# Sheet1.net
KiCad netlist of a schematic drawn in Altium Designer
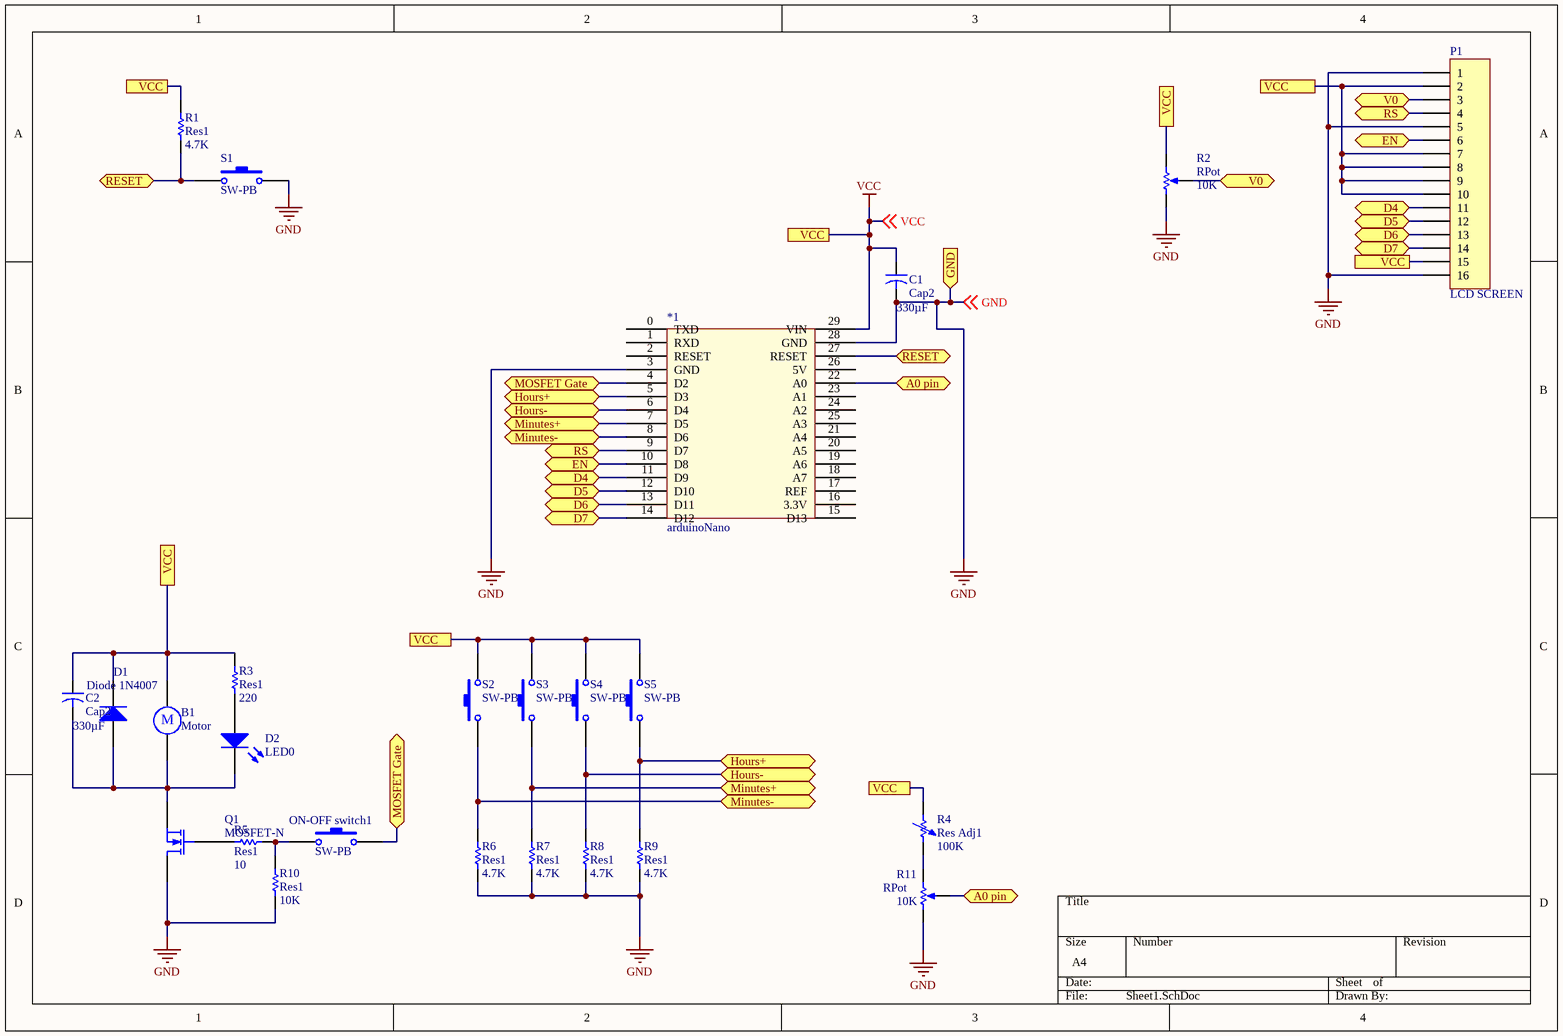
[diagram p0: Sheet1.SchDoc]

(export (version "E")
  (design (tool "Eeschema 10.0.6"))
  (components
    (comp (ref "*1")
      (value "arduinoNano")
      (footprint "Arduino nano")
      (libsource (lib "nanoArduino") (part "arduinoNano"))
    )
    (comp (ref "B1")
      (value "Motor")
      (footprint "RB5-10.5")
      (description "Motor, General Kind")
      (fields (field (name "PUBLISHER") "Altium Limited"))
      (libsource (lib "Miscellaneous Devices") (part "Motor"))
    )
    (comp (ref "C1")
      (value "Cap2")
      (footprint "CAPR5-4X5")
      (description "Capacitor")
      (fields (field (name "ALTIUM_VALUE") "330µF") (field (name "PUBLISHER") "Altium Limited"))
      (libsource (lib "Miscellaneous Devices") (part "Cap2"))
    )
    (comp (ref "C2")
      (value "Cap2")
      (footprint "CAPR5-4X5")
      (description "Capacitor")
      (fields (field (name "ALTIUM_VALUE") "330µF") (field (name "PUBLISHER") "Altium Limited"))
      (libsource (lib "Miscellaneous Devices") (part "Cap2"))
    )
    (comp (ref "D1")
      (value "Diode 1N4007")
      (footprint "DO-41")
      (description "1 Amp General Purpose Rectifier")
      (fields (field (name "PUBLISHER") "Altium Limited"))
      (libsource (lib "Miscellaneous Devices") (part "Diode 1N4007"))
    )
    (comp (ref "D2")
      (value "LED0")
      (footprint "LED-0")
      (description "Typical INFRARED GaAs LED")
      (fields (field (name "PUBLISHER") "Altium Limited"))
      (libsource (lib "Miscellaneous Devices") (part "LED0"))
    )
    (comp (ref "ON-OFF switch1")
      (value "SW-PB")
      (footprint "SPST-2")
      (description "Switch")
      (fields (field (name "PUBLISHER") "Altium Limited"))
      (libsource (lib "Miscellaneous Devices") (part "SW-PB"))
    )
    (comp (ref "P1")
      (value "LCD SCREEN")
      (footprint "HDR1X16")
      (description "Header, 16-Pin")
      (fields (field (name "PUBLISHER") "Altium Limited"))
      (libsource (lib "Miscellaneous Connectors") (part "Header 16"))
    )
    (comp (ref "Q1")
      (value "MOSFET-N")
      (footprint "E3")
      (description "N-Channel MOSFET")
      (fields (field (name "PUBLISHER") "Altium Limited"))
      (libsource (lib "Miscellaneous Devices") (part "MOSFET-N"))
    )
    (comp (ref "R1")
      (value "Res1")
      (footprint "AXIAL-0.3")
      (description "Resistor")
      (fields (field (name "ALTIUM_VALUE") "4.7K") (field (name "PUBLISHER") "Altium Limited"))
      (libsource (lib "Miscellaneous Devices") (part "Res1"))
    )
    (comp (ref "R2")
      (value "RPot")
      (footprint "VR5")
      (description "Potentiometer")
      (fields (field (name "ALTIUM_VALUE") "10K") (field (name "PUBLISHER") "Altium Limited"))
      (libsource (lib "Miscellaneous Devices") (part "RPot"))
    )
    (comp (ref "R3")
      (value "Res1")
      (footprint "AXIAL-0.3")
      (description "Resistor")
      (fields (field (name "ALTIUM_VALUE") "220") (field (name "PUBLISHER") "Altium Limited"))
      (libsource (lib "Miscellaneous Devices") (part "Res1"))
    )
    (comp (ref "R4")
      (value "Res Adj1")
      (footprint "AXIAL-0.7")
      (description "Variable Resistor")
      (fields (field (name "ALTIUM_VALUE") "100K") (field (name "PUBLISHER") "Altium Limited"))
      (libsource (lib "Miscellaneous Devices") (part "Res Adj1"))
    )
    (comp (ref "R5")
      (value "Res1")
      (footprint "AXIAL-0.3")
      (description "Resistor")
      (fields (field (name "ALTIUM_VALUE") "10") (field (name "PUBLISHER") "Altium Limited"))
      (libsource (lib "Miscellaneous Devices") (part "Res1"))
    )
    (comp (ref "R6")
      (value "Res1")
      (footprint "AXIAL-0.3")
      (description "Resistor")
      (fields (field (name "ALTIUM_VALUE") "4.7K") (field (name "PUBLISHER") "Altium Limited"))
      (libsource (lib "Miscellaneous Devices") (part "Res1"))
    )
    (comp (ref "R7")
      (value "Res1")
      (footprint "AXIAL-0.3")
      (description "Resistor")
      (fields (field (name "ALTIUM_VALUE") "4.7K") (field (name "PUBLISHER") "Altium Limited"))
      (libsource (lib "Miscellaneous Devices") (part "Res1"))
    )
    (comp (ref "R8")
      (value "Res1")
      (footprint "AXIAL-0.3")
      (description "Resistor")
      (fields (field (name "ALTIUM_VALUE") "4.7K") (field (name "PUBLISHER") "Altium Limited"))
      (libsource (lib "Miscellaneous Devices") (part "Res1"))
    )
    (comp (ref "R9")
      (value "Res1")
      (footprint "AXIAL-0.3")
      (description "Resistor")
      (fields (field (name "ALTIUM_VALUE") "4.7K") (field (name "PUBLISHER") "Altium Limited"))
      (libsource (lib "Miscellaneous Devices") (part "Res1"))
    )
    (comp (ref "R10")
      (value "Res1")
      (footprint "AXIAL-0.3")
      (description "Resistor")
      (fields (field (name "ALTIUM_VALUE") "10K") (field (name "PUBLISHER") "Altium Limited"))
      (libsource (lib "Miscellaneous Devices") (part "Res1"))
    )
    (comp (ref "R11")
      (value "RPot")
      (footprint "VR5")
      (description "Potentiometer")
      (fields (field (name "ALTIUM_VALUE") "10K") (field (name "PUBLISHER") "Altium Limited"))
      (libsource (lib "Miscellaneous Devices") (part "RPot"))
    )
    (comp (ref "S1")
      (value "SW-PB")
      (footprint "SPST-2")
      (description "Switch")
      (fields (field (name "PUBLISHER") "Altium Limited"))
      (libsource (lib "Miscellaneous Devices") (part "SW-PB"))
    )
    (comp (ref "S2")
      (value "SW-PB")
      (footprint "SPST-2")
      (description "Switch")
      (fields (field (name "PUBLISHER") "Altium Limited"))
      (libsource (lib "Miscellaneous Devices") (part "SW-PB"))
    )
    (comp (ref "S3")
      (value "SW-PB")
      (footprint "SPST-2")
      (description "Switch")
      (fields (field (name "PUBLISHER") "Altium Limited"))
      (libsource (lib "Miscellaneous Devices") (part "SW-PB"))
    )
    (comp (ref "S4")
      (value "SW-PB")
      (footprint "SPST-2")
      (description "Switch")
      (fields (field (name "PUBLISHER") "Altium Limited"))
      (libsource (lib "Miscellaneous Devices") (part "SW-PB"))
    )
    (comp (ref "S5")
      (value "SW-PB")
      (footprint "SPST-2")
      (description "Switch")
      (fields (field (name "PUBLISHER") "Altium Limited"))
      (libsource (lib "Miscellaneous Devices") (part "SW-PB"))
    )
  )
  (nets
    (net (code "1") (name "/A0 pin") (class "Default")
      (node (ref "*1") (pin "22") (pinfunction "A0_22") (pintype "passive"))
      (node (ref "R11") (pin "3") (pinfunction "TAP_3") (pintype "passive"))
    )
    (net (code "2") (name "/D4") (class "Default")
      (node (ref "*1") (pin "11") (pinfunction "D9_11") (pintype "passive"))
      (node (ref "P1") (pin "11") (pinfunction "11_11") (pintype "passive"))
    )
    (net (code "3") (name "/D5") (class "Default")
      (node (ref "*1") (pin "12") (pinfunction "D10_12") (pintype "passive"))
      (node (ref "P1") (pin "12") (pinfunction "12_12") (pintype "passive"))
    )
    (net (code "4") (name "/D6") (class "Default")
      (node (ref "*1") (pin "13") (pinfunction "D11_13") (pintype "passive"))
      (node (ref "P1") (pin "13") (pinfunction "13_13") (pintype "passive"))
    )
    (net (code "5") (name "/D7") (class "Default")
      (node (ref "*1") (pin "14") (pinfunction "D12_14") (pintype "passive"))
      (node (ref "P1") (pin "14") (pinfunction "14_14") (pintype "passive"))
    )
    (net (code "6") (name "/EN") (class "Default")
      (node (ref "*1") (pin "10") (pinfunction "D8_10") (pintype "passive"))
      (node (ref "P1") (pin "6") (pinfunction "6_6") (pintype "passive"))
    )
    (net (code "7") (name "/Hours+") (class "Default")
      (node (ref "*1") (pin "5") (pinfunction "D3_5") (pintype "passive"))
      (node (ref "R9") (pin "2") (pinfunction "2_2") (pintype "passive"))
      (node (ref "S5") (pin "1") (pinfunction "1_1") (pintype "passive"))
    )
    (net (code "8") (name "/Hours-") (class "Default")
      (node (ref "*1") (pin "6") (pinfunction "D4_6") (pintype "passive"))
      (node (ref "R8") (pin "2") (pinfunction "2_2") (pintype "passive"))
      (node (ref "S4") (pin "1") (pinfunction "1_1") (pintype "passive"))
    )
    (net (code "9") (name "/MOSFET Gate") (class "Default")
      (node (ref "*1") (pin "4") (pinfunction "D2_4") (pintype "passive"))
      (node (ref "ON-OFF switch1") (pin "2") (pinfunction "2_2") (pintype "passive"))
    )
    (net (code "10") (name "/Minutes+") (class "Default")
      (node (ref "*1") (pin "7") (pinfunction "D5_7") (pintype "passive"))
      (node (ref "R7") (pin "2") (pinfunction "2_2") (pintype "passive"))
      (node (ref "S3") (pin "1") (pinfunction "1_1") (pintype "passive"))
    )
    (net (code "11") (name "/Minutes-") (class "Default")
      (node (ref "*1") (pin "8") (pinfunction "D6_8") (pintype "passive"))
      (node (ref "R6") (pin "2") (pinfunction "2_2") (pintype "passive"))
      (node (ref "S2") (pin "1") (pinfunction "1_1") (pintype "passive"))
    )
    (net (code "12") (name "/RESET") (class "Default")
      (node (ref "*1") (pin "27") (pinfunction "RESET_27") (pintype "passive"))
      (node (ref "R1") (pin "1") (pinfunction "1_1") (pintype "passive"))
      (node (ref "S1") (pin "1") (pinfunction "1_1") (pintype "passive"))
    )
    (net (code "13") (name "/RS") (class "Default")
      (node (ref "*1") (pin "9") (pinfunction "D7_9") (pintype "passive"))
      (node (ref "P1") (pin "4") (pinfunction "4_4") (pintype "passive"))
    )
    (net (code "14") (name "/V0") (class "Default")
      (node (ref "P1") (pin "3") (pinfunction "3_3") (pintype "passive"))
      (node (ref "R2") (pin "3") (pinfunction "TAP_3") (pintype "passive"))
    )
    (net (code "15") (name "GND") (class "Default")
      (node (ref "*1") (pin "28") (pinfunction "GND_28") (pintype "passive"))
      (node (ref "*1") (pin "3") (pinfunction "GND_3") (pintype "passive"))
      (node (ref "C1") (pin "2") (pinfunction "2_2") (pintype "passive"))
      (node (ref "P1") (pin "1") (pinfunction "1_1") (pintype "passive"))
      (node (ref "P1") (pin "16") (pinfunction "16_16") (pintype "passive"))
      (node (ref "P1") (pin "5") (pinfunction "5_5") (pintype "passive"))
      (node (ref "Q1") (pin "1") (pinfunction "D_1") (pintype "passive"))
      (node (ref "R10") (pin "1") (pinfunction "1_1") (pintype "passive"))
      (node (ref "R11") (pin "1") (pinfunction "TOP_1") (pintype "passive"))
      (node (ref "R2") (pin "1") (pinfunction "TOP_1") (pintype "passive"))
      (node (ref "R6") (pin "1") (pinfunction "1_1") (pintype "passive"))
      (node (ref "R7") (pin "1") (pinfunction "1_1") (pintype "passive"))
      (node (ref "R8") (pin "1") (pinfunction "1_1") (pintype "passive"))
      (node (ref "R9") (pin "1") (pinfunction "1_1") (pintype "passive"))
      (node (ref "S1") (pin "2") (pinfunction "2_2") (pintype "passive"))
    )
    (net (code "16") (name "Net-(D1-A)") (class "Default")
      (node (ref "B1") (pin "2") (pinfunction "2_2") (pintype "passive"))
      (node (ref "C2") (pin "2") (pinfunction "2_2") (pintype "passive"))
      (node (ref "D1") (pin "1") (pinfunction "A_1") (pintype "passive"))
      (node (ref "D2") (pin "2") (pinfunction "K_2") (pintype "passive"))
      (node (ref "Q1") (pin "3") (pinfunction "S_3") (pintype "passive"))
    )
    (net (code "17") (name "Net-(D2-A)") (class "Default")
      (node (ref "D2") (pin "1") (pinfunction "A_1") (pintype "passive"))
      (node (ref "R3") (pin "1") (pinfunction "1_1") (pintype "passive"))
    )
    (net (code "18") (name "Net-(ON-OFF switch1-Pad1)") (class "Default")
      (node (ref "ON-OFF switch1") (pin "1") (pinfunction "1_1") (pintype "passive"))
      (node (ref "R10") (pin "2") (pinfunction "2_2") (pintype "passive"))
      (node (ref "R5") (pin "2") (pinfunction "2_2") (pintype "passive"))
    )
    (net (code "19") (name "Net-(Q1-G)") (class "Default")
      (node (ref "Q1") (pin "2") (pinfunction "G_2") (pintype "passive"))
      (node (ref "R5") (pin "1") (pinfunction "1_1") (pintype "passive"))
    )
    (net (code "20") (name "Net-(R11-BOT)") (class "Default")
      (node (ref "R11") (pin "2") (pinfunction "BOT_2") (pintype "passive"))
      (node (ref "R4") (pin "2") (pinfunction "2_2") (pintype "passive"))
    )
    (net (code "21") (name "VCC") (class "Default")
      (node (ref "*1") (pin "29") (pinfunction "VIN_29") (pintype "passive"))
      (node (ref "B1") (pin "1") (pinfunction "1_1") (pintype "passive"))
      (node (ref "C1") (pin "1") (pinfunction "1_1") (pintype "passive"))
      (node (ref "C2") (pin "1") (pinfunction "1_1") (pintype "passive"))
      (node (ref "D1") (pin "2") (pinfunction "K_2") (pintype "passive"))
      (node (ref "P1") (pin "10") (pinfunction "10_10") (pintype "passive"))
      (node (ref "P1") (pin "15") (pinfunction "15_15") (pintype "passive"))
      (node (ref "P1") (pin "2") (pinfunction "2_2") (pintype "passive"))
      (node (ref "P1") (pin "7") (pinfunction "7_7") (pintype "passive"))
      (node (ref "P1") (pin "8") (pinfunction "8_8") (pintype "passive"))
      (node (ref "P1") (pin "9") (pinfunction "9_9") (pintype "passive"))
      (node (ref "R1") (pin "2") (pinfunction "2_2") (pintype "passive"))
      (node (ref "R2") (pin "2") (pinfunction "BOT_2") (pintype "passive"))
      (node (ref "R3") (pin "2") (pinfunction "2_2") (pintype "passive"))
      (node (ref "R4") (pin "1") (pinfunction "1_1") (pintype "passive"))
      (node (ref "S2") (pin "2") (pinfunction "2_2") (pintype "passive"))
      (node (ref "S3") (pin "2") (pinfunction "2_2") (pintype "passive"))
      (node (ref "S4") (pin "2") (pinfunction "2_2") (pintype "passive"))
      (node (ref "S5") (pin "2") (pinfunction "2_2") (pintype "passive"))
    )
    (net (code "22") (name "unconnected-(*1-3.3V-Pad16)") (class "Default")
      (node (ref "*1") (pin "16") (pinfunction "3.3V_16") (pintype "passive"))
    )
    (net (code "23") (name "unconnected-(*1-5V-Pad26)") (class "Default")
      (node (ref "*1") (pin "26") (pinfunction "5V_26") (pintype "passive"))
    )
    (net (code "24") (name "unconnected-(*1-A1-Pad23)") (class "Default")
      (node (ref "*1") (pin "23") (pinfunction "A1_23") (pintype "passive"))
    )
    (net (code "25") (name "unconnected-(*1-A2-Pad24)") (class "Default")
      (node (ref "*1") (pin "24") (pinfunction "A2_24") (pintype "passive"))
    )
    (net (code "26") (name "unconnected-(*1-A3-Pad25)") (class "Default")
      (node (ref "*1") (pin "25") (pinfunction "A3_25") (pintype "passive"))
    )
    (net (code "27") (name "unconnected-(*1-A4-Pad21)") (class "Default")
      (node (ref "*1") (pin "21") (pinfunction "A4_21") (pintype "passive"))
    )
    (net (code "28") (name "unconnected-(*1-A5-Pad20)") (class "Default")
      (node (ref "*1") (pin "20") (pinfunction "A5_20") (pintype "passive"))
    )
    (net (code "29") (name "unconnected-(*1-A6-Pad19)") (class "Default")
      (node (ref "*1") (pin "19") (pinfunction "A6_19") (pintype "passive"))
    )
    (net (code "30") (name "unconnected-(*1-A7-Pad18)") (class "Default")
      (node (ref "*1") (pin "18") (pinfunction "A7_18") (pintype "passive"))
    )
    (net (code "31") (name "unconnected-(*1-D13-Pad15)") (class "Default")
      (node (ref "*1") (pin "15") (pinfunction "D13_15") (pintype "passive"))
    )
    (net (code "32") (name "unconnected-(*1-REF-Pad17)") (class "Default")
      (node (ref "*1") (pin "17") (pinfunction "REF_17") (pintype "passive"))
    )
    (net (code "33") (name "unconnected-(*1-RESET-Pad2)") (class "Default")
      (node (ref "*1") (pin "2") (pinfunction "RESET_2") (pintype "passive"))
    )
    (net (code "34") (name "unconnected-(*1-RXD-Pad1)") (class "Default")
      (node (ref "*1") (pin "1") (pinfunction "RXD_1") (pintype "passive"))
    )
    (net (code "35") (name "unconnected-(*1-TXD-Pad0)") (class "Default")
      (node (ref "*1") (pin "0") (pinfunction "TXD_0") (pintype "passive"))
    )
  )
)
